# single_channel_-_Rev_C_-_Part_1.net
KiCad netlist of a schematic drawn in EAGLE
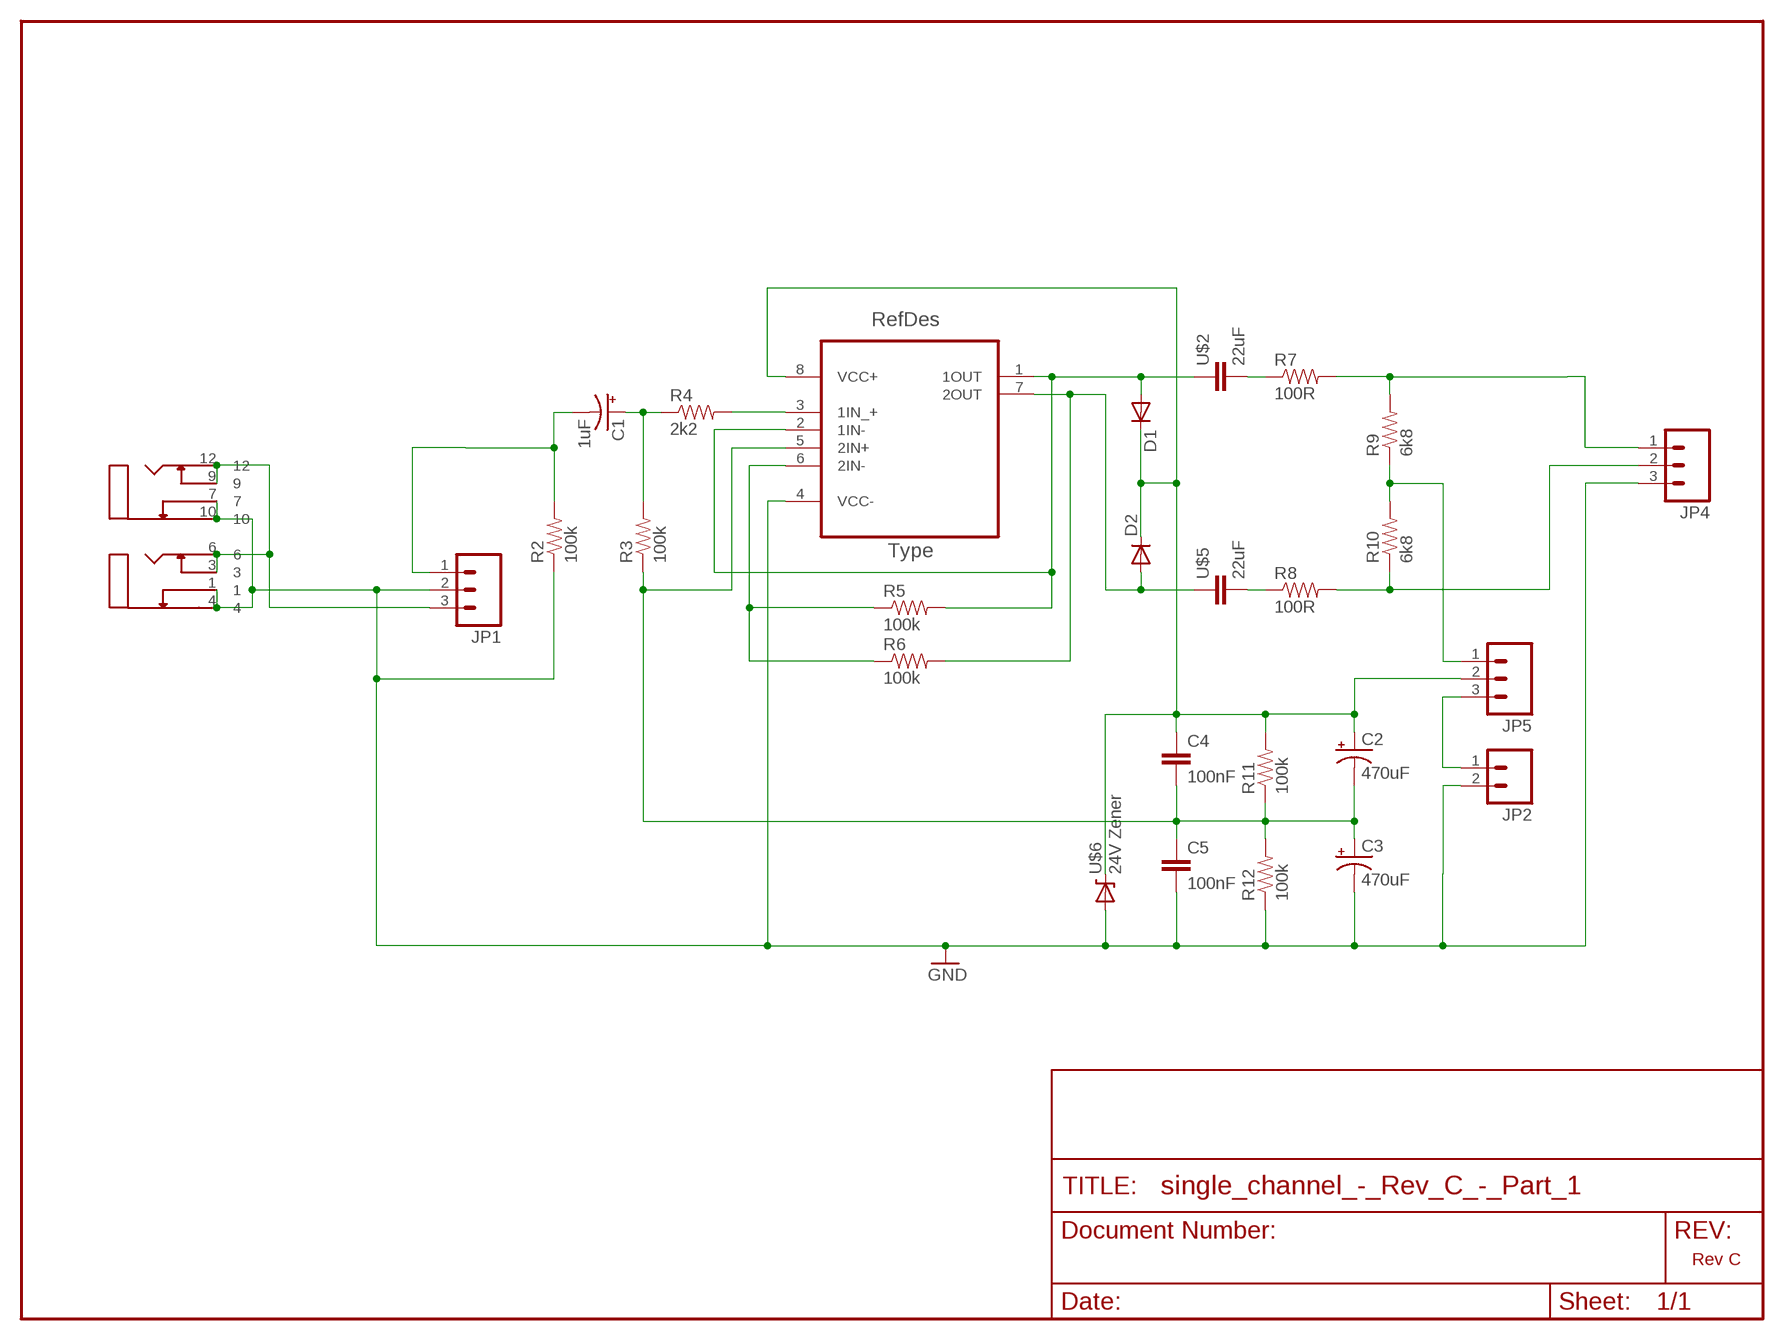
[diagram p0: schematic, sheet 1]

(export (version "E")
  (design (tool "Eeschema 10.0.6"))
  (components
    (comp (ref "C1")
      (value "1uF")
      (footprint "eagle-import:CPOL-RADIAL-10UF-25V")
      (libsource (lib "eagle-import") (part "CAP_POLPTH2"))
    )
    (comp (ref "C2")
      (value "470uF")
      (footprint "eagle-import:CPOL-RADIAL-1000UF-25V")
      (libsource (lib "eagle-import") (part "SparkFun-Passives_CAP_POLPTH4"))
    )
    (comp (ref "C3")
      (value "470uF")
      (footprint "eagle-import:CPOL-RADIAL-1000UF-25V")
      (libsource (lib "eagle-import") (part "SparkFun-Passives_CAP_POLPTH4"))
    )
    (comp (ref "C4")
      (value "100nF")
      (footprint "eagle-import:CAP-PTH-5MM")
      (libsource (lib "eagle-import") (part "CAPPTH1"))
    )
    (comp (ref "C5")
      (value "100nF")
      (footprint "eagle-import:CAP-PTH-5MM")
      (libsource (lib "eagle-import") (part "CAPPTH1"))
    )
    (comp (ref "D1")
      (value "DIODE1N4148")
      (footprint "eagle-import:DIODE-1N4148")
      (libsource (lib "eagle-import") (part "DIODE1N4148"))
    )
    (comp (ref "D2")
      (value "DIODE1N4148")
      (footprint "eagle-import:DIODE-1N4148")
      (libsource (lib "eagle-import") (part "DIODE1N4148"))
    )
    (comp (ref "J1")
      (value "ACJMMHD")
      (footprint "eagle-import:MHD")
      (libsource (lib "eagle-import") (part "ACJMMHD"))
    )
    (comp (ref "JP1")
      (value "M03LONGPADS")
      (footprint "eagle-import:1X03_LONGPADS")
      (libsource (lib "eagle-import") (part "M03LONGPADS"))
    )
    (comp (ref "JP2")
      (value "M02PTH3")
      (footprint "eagle-import:1X02_LONGPADS")
      (libsource (lib "eagle-import") (part "M02PTH3"))
    )
    (comp (ref "JP4")
      (value "M03LONGPADS")
      (footprint "eagle-import:1X03_LONGPADS")
      (libsource (lib "eagle-import") (part "M03LONGPADS"))
    )
    (comp (ref "JP5")
      (value "M03LONGPADS")
      (footprint "eagle-import:1X03_LONGPADS")
      (libsource (lib "eagle-import") (part "M03LONGPADS"))
    )
    (comp (ref "R2")
      (value "100k")
      (footprint "eagle-import:AXIAL-0.5")
      (libsource (lib "eagle-import") (part "RESISTORPTH-1/2W"))
    )
    (comp (ref "R3")
      (value "100k")
      (footprint "eagle-import:AXIAL-0.5")
      (libsource (lib "eagle-import") (part "RESISTORPTH-1/2W"))
    )
    (comp (ref "R4")
      (value "2k2")
      (footprint "eagle-import:AXIAL-0.5")
      (libsource (lib "eagle-import") (part "RESISTORPTH-1/2W"))
    )
    (comp (ref "R5")
      (value "100k")
      (footprint "eagle-import:AXIAL-0.5")
      (libsource (lib "eagle-import") (part "RESISTORPTH-1/2W"))
    )
    (comp (ref "R6")
      (value "100k")
      (footprint "eagle-import:AXIAL-0.5")
      (libsource (lib "eagle-import") (part "RESISTORPTH-1/2W"))
    )
    (comp (ref "R7")
      (value "100R")
      (footprint "eagle-import:AXIAL-0.5")
      (libsource (lib "eagle-import") (part "RESISTORPTH-1/2W"))
    )
    (comp (ref "R8")
      (value "100R")
      (footprint "eagle-import:AXIAL-0.5")
      (libsource (lib "eagle-import") (part "RESISTORPTH-1/2W"))
    )
    (comp (ref "R9")
      (value "6k8")
      (footprint "eagle-import:AXIAL-0.5")
      (libsource (lib "eagle-import") (part "RESISTORPTH-1/2W"))
    )
    (comp (ref "R10")
      (value "6k8")
      (footprint "eagle-import:AXIAL-0.5")
      (libsource (lib "eagle-import") (part "RESISTORPTH-1/2W"))
    )
    (comp (ref "R11")
      (value "100k")
      (footprint "eagle-import:AXIAL-0.5")
      (libsource (lib "eagle-import") (part "RESISTORPTH-1/2W"))
    )
    (comp (ref "R12")
      (value "100k")
      (footprint "eagle-import:AXIAL-0.5")
      (libsource (lib "eagle-import") (part "RESISTORPTH-1/2W"))
    )
    (comp (ref "U$2")
      (value "22uF")
      (footprint "eagle-import:8MM")
      (libsource (lib "eagle-import") (part "CAP8MM"))
    )
    (comp (ref "U$5")
      (value "22uF")
      (footprint "eagle-import:8MM")
      (libsource (lib "eagle-import") (part "CAP8MM"))
    )
    (comp (ref "U$6")
      (value "24V Zener")
      (footprint "eagle-import:DIODE-ZENER")
      (libsource (lib "eagle-import") (part "DIODE-ZENERPTH"))
    )
    (comp (ref "U1")
      (value "TL072CP")
      (footprint "eagle-import:DIP254P762X508-8")
      (libsource (lib "eagle-import") (part "TL072CP"))
    )
  )
  (nets
    (net (code "1") (name "GND") (class "Default")
      (node (ref "C3") (pin "2") (pinfunction "-_2") (pintype "passive"))
      (node (ref "C5") (pin "2") (pinfunction "2_2") (pintype "passive"))
      (node (ref "J1") (pin "1") (pinfunction "1_1") (pintype "bidirectional"))
      (node (ref "J1") (pin "10") (pinfunction "10_10") (pintype "bidirectional"))
      (node (ref "J1") (pin "4") (pinfunction "4_4") (pintype "bidirectional"))
      (node (ref "J1") (pin "7") (pinfunction "7_7") (pintype "bidirectional"))
      (node (ref "JP1") (pin "2") (pinfunction "2_2") (pintype "passive"))
      (node (ref "JP2") (pin "2") (pinfunction "2_2") (pintype "passive"))
      (node (ref "JP4") (pin "3") (pinfunction "3_3") (pintype "passive"))
      (node (ref "R12") (pin "P$1") (pinfunction "1_P$1") (pintype "passive"))
      (node (ref "R2") (pin "P$1") (pinfunction "1_P$1") (pintype "passive"))
      (node (ref "U$6") (pin "P$2") (pinfunction "A_P$2") (pintype "passive"))
      (node (ref "U1") (pin "4") (pinfunction "VCC-_4") (pintype "passive"))
    )
    (net (code "2") (name "Net-(C1-+)") (class "Default")
      (node (ref "C1") (pin "1") (pinfunction "+_1") (pintype "passive"))
      (node (ref "R3") (pin "P$2") (pinfunction "2_P$2") (pintype "passive"))
      (node (ref "R4") (pin "P$1") (pinfunction "1_P$1") (pintype "passive"))
    )
    (net (code "3") (name "Net-(C1--)") (class "Default")
      (node (ref "C1") (pin "2") (pinfunction "-_2") (pintype "passive"))
      (node (ref "JP1") (pin "1") (pinfunction "1_1") (pintype "passive"))
      (node (ref "R2") (pin "P$2") (pinfunction "2_P$2") (pintype "passive"))
    )
    (net (code "4") (name "Net-(C2-+)") (class "Default")
      (node (ref "C2") (pin "1") (pinfunction "+_1") (pintype "passive"))
      (node (ref "C4") (pin "1") (pinfunction "1_1") (pintype "passive"))
      (node (ref "D1") (pin "C") (pinfunction "C_C") (pintype "passive"))
      (node (ref "D2") (pin "C") (pinfunction "C_C") (pintype "passive"))
      (node (ref "JP5") (pin "2") (pinfunction "2_2") (pintype "passive"))
      (node (ref "R11") (pin "P$2") (pinfunction "2_P$2") (pintype "passive"))
      (node (ref "U$6") (pin "P$1") (pinfunction "C_P$1") (pintype "passive"))
      (node (ref "U1") (pin "8") (pinfunction "VCC+_8") (pintype "power_in"))
    )
    (net (code "5") (name "Net-(C2--)") (class "Default")
      (node (ref "C2") (pin "2") (pinfunction "-_2") (pintype "passive"))
      (node (ref "C3") (pin "1") (pinfunction "+_1") (pintype "passive"))
      (node (ref "C4") (pin "2") (pinfunction "2_2") (pintype "passive"))
      (node (ref "C5") (pin "1") (pinfunction "1_1") (pintype "passive"))
      (node (ref "R11") (pin "P$1") (pinfunction "1_P$1") (pintype "passive"))
      (node (ref "R12") (pin "P$2") (pinfunction "2_P$2") (pintype "passive"))
      (node (ref "R3") (pin "P$1") (pinfunction "1_P$1") (pintype "passive"))
      (node (ref "U1") (pin "5") (pinfunction "2IN+_5") (pintype "input"))
    )
    (net (code "6") (name "Net-(J1-Pad12)") (class "Default")
      (node (ref "J1") (pin "12") (pinfunction "12_12") (pintype "bidirectional"))
      (node (ref "J1") (pin "3") (pinfunction "3_3") (pintype "bidirectional"))
      (node (ref "J1") (pin "6") (pinfunction "6_6") (pintype "bidirectional"))
      (node (ref "J1") (pin "9") (pinfunction "9_9") (pintype "bidirectional"))
      (node (ref "JP1") (pin "3") (pinfunction "3_3") (pintype "passive"))
    )
    (net (code "7") (name "Net-(JP2-Pad1)") (class "Default")
      (node (ref "JP2") (pin "1") (pinfunction "1_1") (pintype "passive"))
      (node (ref "JP5") (pin "3") (pinfunction "3_3") (pintype "passive"))
    )
    (net (code "8") (name "Net-(R4-2)") (class "Default")
      (node (ref "R4") (pin "P$2") (pinfunction "2_P$2") (pintype "passive"))
      (node (ref "U1") (pin "3") (pinfunction "1IN_+_3") (pintype "input"))
    )
    (net (code "9") (name "Net-(R5-1)") (class "Default")
      (node (ref "R5") (pin "P$1") (pinfunction "1_P$1") (pintype "passive"))
      (node (ref "R6") (pin "P$1") (pinfunction "1_P$1") (pintype "passive"))
      (node (ref "U1") (pin "6") (pinfunction "2IN-_6") (pintype "input"))
    )
    (net (code "10") (name "Net-(R5-2)") (class "Default")
      (node (ref "D1") (pin "A") (pinfunction "A_A") (pintype "passive"))
      (node (ref "R5") (pin "P$2") (pinfunction "2_P$2") (pintype "passive"))
      (node (ref "U$2") (pin "P$1") (pinfunction "1_P$1") (pintype "passive"))
      (node (ref "U1") (pin "1") (pinfunction "1OUT_1") (pintype "output"))
      (node (ref "U1") (pin "2") (pinfunction "1IN-_2") (pintype "input"))
    )
    (net (code "11") (name "Net-(R6-2)") (class "Default")
      (node (ref "D2") (pin "A") (pinfunction "A_A") (pintype "passive"))
      (node (ref "R6") (pin "P$2") (pinfunction "2_P$2") (pintype "passive"))
      (node (ref "U$5") (pin "P$1") (pinfunction "1_P$1") (pintype "passive"))
      (node (ref "U1") (pin "7") (pinfunction "2OUT_7") (pintype "output"))
    )
    (net (code "12") (name "Net-(R7-1)") (class "Default")
      (node (ref "R7") (pin "P$1") (pinfunction "1_P$1") (pintype "passive"))
      (node (ref "U$2") (pin "P$2") (pinfunction "2_P$2") (pintype "passive"))
    )
    (net (code "13") (name "Net-(R7-2)") (class "Default")
      (node (ref "JP4") (pin "1") (pinfunction "1_1") (pintype "passive"))
      (node (ref "R7") (pin "P$2") (pinfunction "2_P$2") (pintype "passive"))
      (node (ref "R9") (pin "P$2") (pinfunction "2_P$2") (pintype "passive"))
    )
    (net (code "14") (name "Net-(R8-1)") (class "Default")
      (node (ref "R8") (pin "P$1") (pinfunction "1_P$1") (pintype "passive"))
      (node (ref "U$5") (pin "P$2") (pinfunction "2_P$2") (pintype "passive"))
    )
    (net (code "15") (name "Net-(R10-1)") (class "Default")
      (node (ref "JP4") (pin "2") (pinfunction "2_2") (pintype "passive"))
      (node (ref "R10") (pin "P$1") (pinfunction "1_P$1") (pintype "passive"))
      (node (ref "R8") (pin "P$2") (pinfunction "2_P$2") (pintype "passive"))
    )
    (net (code "16") (name "Net-(R10-2)") (class "Default")
      (node (ref "JP5") (pin "1") (pinfunction "1_1") (pintype "passive"))
      (node (ref "R10") (pin "P$2") (pinfunction "2_P$2") (pintype "passive"))
      (node (ref "R9") (pin "P$1") (pinfunction "1_P$1") (pintype "passive"))
    )
  )
)
